# Crossover.net
KiCad netlist of a schematic drawn in Altium Designer
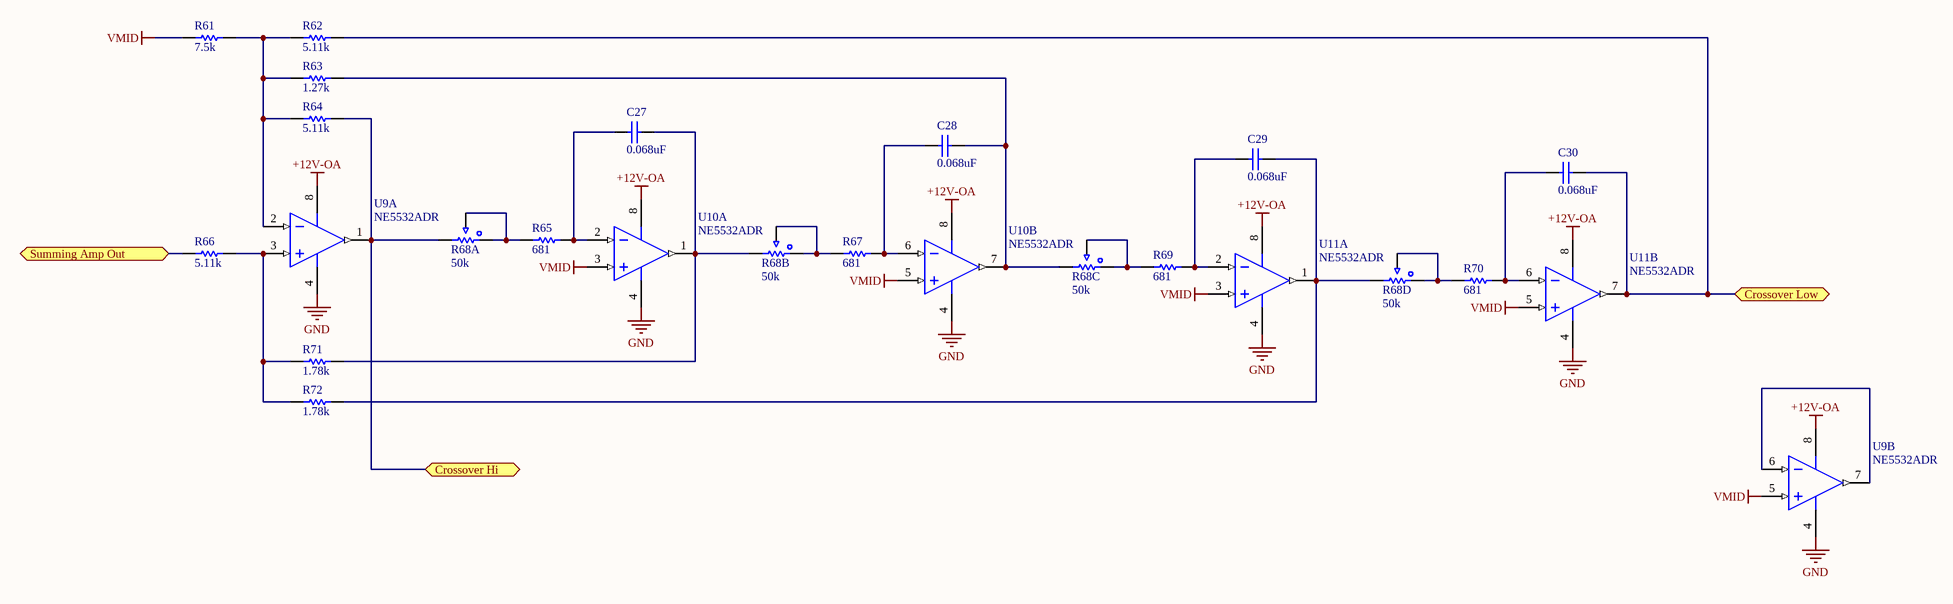
[diagram p0: Crossover.SchDoc]

(export (version "E")
  (design (tool "Eeschema 10.0.6"))
  (components
    (comp (ref "C27")
      (value "0.068uF")
      (footprint "RESC3216X70X50NL05T20")
      (description "C Series 1206 50 V 0.068 uF ±5% Tolerance C0G SMT Multilayer Ceramic Capacitor")
      (libsource (lib "CommunityVault") (part "SYM-f94231c42cf32685-1"))
    )
    (comp (ref "C28")
      (value "0.068uF")
      (footprint "RESC3216X70X50NL05T20")
      (description "C Series 1206 50 V 0.068 uF ±5% Tolerance C0G SMT Multilayer Ceramic Capacitor")
      (libsource (lib "CommunityVault") (part "SYM-f94231c42cf32685-1"))
    )
    (comp (ref "C29")
      (value "0.068uF")
      (footprint "RESC3216X70X50NL05T20")
      (description "C Series 1206 50 V 0.068 uF ±5% Tolerance C0G SMT Multilayer Ceramic Capacitor")
      (libsource (lib "CommunityVault") (part "SYM-f94231c42cf32685-1"))
    )
    (comp (ref "C30")
      (value "0.068uF")
      (footprint "RESC3216X70X50NL05T20")
      (description "C Series 1206 50 V 0.068 uF ±5% Tolerance C0G SMT Multilayer Ceramic Capacitor")
      (libsource (lib "CommunityVault") (part "SYM-f94231c42cf32685-1"))
    )
    (comp (ref "R61")
      (value "7.5k")
      (footprint "RESC1609X55X28LL05T18")
      (description "Res Thin Film 0603 7.5K Ohm 0.1% 0.1W(1/10W) ±25ppm/C SMD Automotive T/R")
      (fields
        (field (name "MANUFACTURER") "Vishay")
        (field (name "MANUFACTURER PART NUMBER") "MCT0603MD7501BP100")
      )
      (libsource (lib "CommunityVault") (part "SYM-2e48e5fbd8dbf18f-1"))
    )
    (comp (ref "R62")
      (value "5.11k")
      (footprint "PCB-dm6f2vlmfnf97yy2nsh5-1")
      (description "Res Thin Film 0603 5.11K Ohm 0.1% 1/10W ±25ppm/°C Molded SMD SMD Paper T/R")
      (fields (field (name "MANUFACTURER PART NUMBER") "MCT06030D5111BP100"))
      (libsource (lib "CommunityVault") (part "SYM-3220f9ecb51bede7-1"))
    )
    (comp (ref "R63")
      (value "1.27k")
      (footprint "RESC1609X55X28LL05T18")
      (description "Res Thin Film 0603 1.27K Ohm 0.1% 1/10W ±25ppm/°C Molded SMD SMD Paper T/R")
      (fields (field (name "MANUFACTURER PART NUMBER") "MCT06030D1271BP100"))
      (libsource (lib "CommunityVault") (part "SYM-169edd529233c959-1"))
    )
    (comp (ref "R64")
      (value "5.11k")
      (footprint "PCB-dm6f2vlmfnf97yy2nsh5-1")
      (description "Res Thin Film 0603 5.11K Ohm 0.1% 1/10W ±25ppm/°C Molded SMD SMD Paper T/R")
      (fields (field (name "MANUFACTURER PART NUMBER") "MCT06030D5111BP100"))
      (libsource (lib "CommunityVault") (part "SYM-3220f9ecb51bede7-1"))
    )
    (comp (ref "R65")
      (value "681")
      (footprint "RESC1609X55X28LL05T18")
      (description "Res Thin Film 0603 681 Ohm 0.1% 1/10W ±25ppm/°C Molded SMD SMD Paper T/R")
      (libsource (lib "CommunityVault") (part "SYM-437288bec46a9cb5-1"))
    )
    (comp (ref "R66")
      (value "5.11k")
      (footprint "PCB-dm6f2vlmfnf97yy2nsh5-1")
      (description "Res Thin Film 0603 5.11K Ohm 0.1% 1/10W ±25ppm/°C Molded SMD SMD Paper T/R")
      (fields (field (name "MANUFACTURER PART NUMBER") "MCT06030D5111BP100"))
      (libsource (lib "CommunityVault") (part "SYM-3220f9ecb51bede7-1"))
    )
    (comp (ref "R67")
      (value "681")
      (footprint "RESC1609X55X28LL05T18")
      (description "Res Thin Film 0603 681 Ohm 0.1% 1/10W ±25ppm/°C Molded SMD SMD Paper T/R")
      (libsource (lib "CommunityVault") (part "SYM-437288bec46a9cb5-1"))
    )
    (comp (ref "R68")
      (value "50k")
      (footprint "PCB-3c7eria7znpasna51pjn-1")
      (libsource (lib "") (part "CMP-1b48d3c31cb2c48f-2_2"))
    )
    (comp (ref "R69")
      (value "681")
      (footprint "RESC1609X55X28LL05T18")
      (description "Res Thin Film 0603 681 Ohm 0.1% 1/10W ±25ppm/°C Molded SMD SMD Paper T/R")
      (libsource (lib "CommunityVault") (part "SYM-437288bec46a9cb5-1"))
    )
    (comp (ref "R70")
      (value "681")
      (footprint "RESC1609X55X28LL05T18")
      (description "Res Thin Film 0603 681 Ohm 0.1% 1/10W ±25ppm/°C Molded SMD SMD Paper T/R")
      (libsource (lib "CommunityVault") (part "SYM-437288bec46a9cb5-1"))
    )
    (comp (ref "R71")
      (value "1.78k")
      (footprint "RESC1609X55X28LL05T18")
      (description "Res Thin Film 0603 1.78K Ohm 0.1% 1/10W ±25ppm/°C Molded SMD Paper T/R")
      (libsource (lib "CommunityVault") (part "SYM-0169caa585e3deae-1"))
    )
    (comp (ref "R72")
      (value "1.78k")
      (footprint "RESC1609X55X28LL05T18")
      (description "Res Thin Film 0603 1.78K Ohm 0.1% 1/10W ±25ppm/°C Molded SMD Paper T/R")
      (libsource (lib "CommunityVault") (part "SYM-0169caa585e3deae-1"))
    )
    (comp (ref "U9")
      (value "NE5532ADR")
      (footprint "TI-D8_L")
      (libsource (lib "CommunityVault") (part "CMP-13597030-2"))
    )
    (comp (ref "U10")
      (value "NE5532ADR")
      (footprint "TI-D8_L")
      (libsource (lib "CommunityVault") (part "CMP-13597030-2"))
    )
    (comp (ref "U11")
      (value "NE5532ADR")
      (footprint "TI-D8_L")
      (libsource (lib "CommunityVault") (part "CMP-13597030-2"))
    )
  )
  (nets
    (net (code "1") (name "+12V-OA") (class "Default")
      (node (ref "U10") (pin "8") (pinfunction "VCC+_8") (pintype "power_in"))
      (node (ref "U11") (pin "8") (pinfunction "VCC+_8") (pintype "power_in"))
      (node (ref "U9") (pin "8") (pinfunction "VCC+_8") (pintype "power_in"))
    )
    (net (code "2") (name "/Crossover Hi") (class "Default")
      (node (ref "R64") (pin "2") (pinfunction "2_2") (pintype "passive"))
      (node (ref "R68") (pin "R1_3") (pinfunction "R1_3_R1_3") (pintype "passive"))
      (node (ref "U9") (pin "1") (pinfunction "OUT1_1") (pintype "output"))
    )
    (net (code "3") (name "/Crossover Low") (class "Default")
      (node (ref "C30") (pin "2") (pinfunction "2_2") (pintype "passive"))
      (node (ref "R62") (pin "2") (pinfunction "2_2") (pintype "passive"))
      (node (ref "U11") (pin "7") (pinfunction "OUT2_7") (pintype "output"))
    )
    (net (code "4") (name "/Summing Amp Out") (class "Default")
      (node (ref "R66") (pin "1") (pinfunction "1_1") (pintype "passive"))
    )
    (net (code "5") (name "GND") (class "Default")
      (node (ref "U10") (pin "4") (pinfunction "VCC-_4") (pintype "power_in"))
      (node (ref "U11") (pin "4") (pinfunction "VCC-_4") (pintype "power_in"))
      (node (ref "U9") (pin "4") (pinfunction "VCC-_4") (pintype "power_in"))
    )
    (net (code "6") (name "Net-(R65-Pad1)") (class "Default")
      (node (ref "R65") (pin "1") (pinfunction "1_1") (pintype "passive"))
      (node (ref "R68") (pin "R1_1") (pinfunction "R1_1_R1_1") (pintype "passive"))
      (node (ref "R68") (pin "R1_2") (pinfunction "R1_2_R1_2") (pintype "passive"))
    )
    (net (code "7") (name "Net-(R67-Pad1)") (class "Default")
      (node (ref "R67") (pin "1") (pinfunction "1_1") (pintype "passive"))
      (node (ref "R68") (pin "R2_1") (pinfunction "R2_1_R2_1") (pintype "passive"))
      (node (ref "R68") (pin "R2_2") (pinfunction "R2_2_R2_2") (pintype "passive"))
    )
    (net (code "8") (name "Net-(R68-PadR3_1)") (class "Default")
      (node (ref "R68") (pin "R3_1") (pinfunction "R3_1_R3_1") (pintype "passive"))
      (node (ref "R68") (pin "R3_2") (pinfunction "R3_2_R3_2") (pintype "passive"))
      (node (ref "R69") (pin "1") (pinfunction "1_1") (pintype "passive"))
    )
    (net (code "9") (name "Net-(R68-PadR4_1)") (class "Default")
      (node (ref "R68") (pin "R4_1") (pinfunction "R4_1_R4_1") (pintype "passive"))
      (node (ref "R68") (pin "R4_2") (pinfunction "R4_2_R4_2") (pintype "passive"))
      (node (ref "R70") (pin "1") (pinfunction "1_1") (pintype "passive"))
    )
    (net (code "10") (name "Net-(U9A-IN1+)") (class "Default")
      (node (ref "R66") (pin "2") (pinfunction "2_2") (pintype "passive"))
      (node (ref "R71") (pin "1") (pinfunction "1_1") (pintype "passive"))
      (node (ref "R72") (pin "1") (pinfunction "1_1") (pintype "passive"))
      (node (ref "U9") (pin "3") (pinfunction "IN1+_3") (pintype "input"))
    )
    (net (code "11") (name "Net-(U9A-IN1-)") (class "Default")
      (node (ref "R61") (pin "2") (pinfunction "2_2") (pintype "passive"))
      (node (ref "R62") (pin "1") (pinfunction "1_1") (pintype "passive"))
      (node (ref "R63") (pin "1") (pinfunction "1_1") (pintype "passive"))
      (node (ref "R64") (pin "1") (pinfunction "1_1") (pintype "passive"))
      (node (ref "U9") (pin "2") (pinfunction "IN1-_2") (pintype "input"))
    )
    (net (code "12") (name "Net-(U9B-IN2-)") (class "Default")
      (node (ref "U9") (pin "6") (pinfunction "IN2-_6") (pintype "input"))
      (node (ref "U9") (pin "7") (pinfunction "OUT2_7") (pintype "output"))
    )
    (net (code "13") (name "Net-(U10A-IN1-)") (class "Default")
      (node (ref "C27") (pin "1") (pinfunction "1_1") (pintype "passive"))
      (node (ref "R65") (pin "2") (pinfunction "2_2") (pintype "passive"))
      (node (ref "U10") (pin "2") (pinfunction "IN1-_2") (pintype "input"))
    )
    (net (code "14") (name "Net-(U10A-OUT1)") (class "Default")
      (node (ref "C27") (pin "2") (pinfunction "2_2") (pintype "passive"))
      (node (ref "R68") (pin "R2_3") (pinfunction "R2_3_R2_3") (pintype "passive"))
      (node (ref "R71") (pin "2") (pinfunction "2_2") (pintype "passive"))
      (node (ref "U10") (pin "1") (pinfunction "OUT1_1") (pintype "output"))
    )
    (net (code "15") (name "Net-(U10B-IN2-)") (class "Default")
      (node (ref "C28") (pin "1") (pinfunction "1_1") (pintype "passive"))
      (node (ref "R67") (pin "2") (pinfunction "2_2") (pintype "passive"))
      (node (ref "U10") (pin "6") (pinfunction "IN2-_6") (pintype "input"))
    )
    (net (code "16") (name "Net-(U10B-OUT2)") (class "Default")
      (node (ref "C28") (pin "2") (pinfunction "2_2") (pintype "passive"))
      (node (ref "R63") (pin "2") (pinfunction "2_2") (pintype "passive"))
      (node (ref "R68") (pin "R3_3") (pinfunction "R3_3_R3_3") (pintype "passive"))
      (node (ref "U10") (pin "7") (pinfunction "OUT2_7") (pintype "output"))
    )
    (net (code "17") (name "Net-(U11A-IN1-)") (class "Default")
      (node (ref "C29") (pin "1") (pinfunction "1_1") (pintype "passive"))
      (node (ref "R69") (pin "2") (pinfunction "2_2") (pintype "passive"))
      (node (ref "U11") (pin "2") (pinfunction "IN1-_2") (pintype "input"))
    )
    (net (code "18") (name "Net-(U11A-OUT1)") (class "Default")
      (node (ref "C29") (pin "2") (pinfunction "2_2") (pintype "passive"))
      (node (ref "R68") (pin "R4_3") (pinfunction "R4_3_R4_3") (pintype "passive"))
      (node (ref "R72") (pin "2") (pinfunction "2_2") (pintype "passive"))
      (node (ref "U11") (pin "1") (pinfunction "OUT1_1") (pintype "output"))
    )
    (net (code "19") (name "Net-(U11B-IN2-)") (class "Default")
      (node (ref "C30") (pin "1") (pinfunction "1_1") (pintype "passive"))
      (node (ref "R70") (pin "2") (pinfunction "2_2") (pintype "passive"))
      (node (ref "U11") (pin "6") (pinfunction "IN2-_6") (pintype "input"))
    )
    (net (code "20") (name "VMID") (class "Default")
      (node (ref "R61") (pin "1") (pinfunction "1_1") (pintype "passive"))
      (node (ref "U10") (pin "3") (pinfunction "IN1+_3") (pintype "input"))
      (node (ref "U10") (pin "5") (pinfunction "IN2+_5") (pintype "input"))
      (node (ref "U11") (pin "3") (pinfunction "IN1+_3") (pintype "input"))
      (node (ref "U11") (pin "5") (pinfunction "IN2+_5") (pintype "input"))
      (node (ref "U9") (pin "5") (pinfunction "IN2+_5") (pintype "input"))
    )
  )
)
